# OxygenSensor.net
KiCad netlist of a schematic drawn in Altium Designer
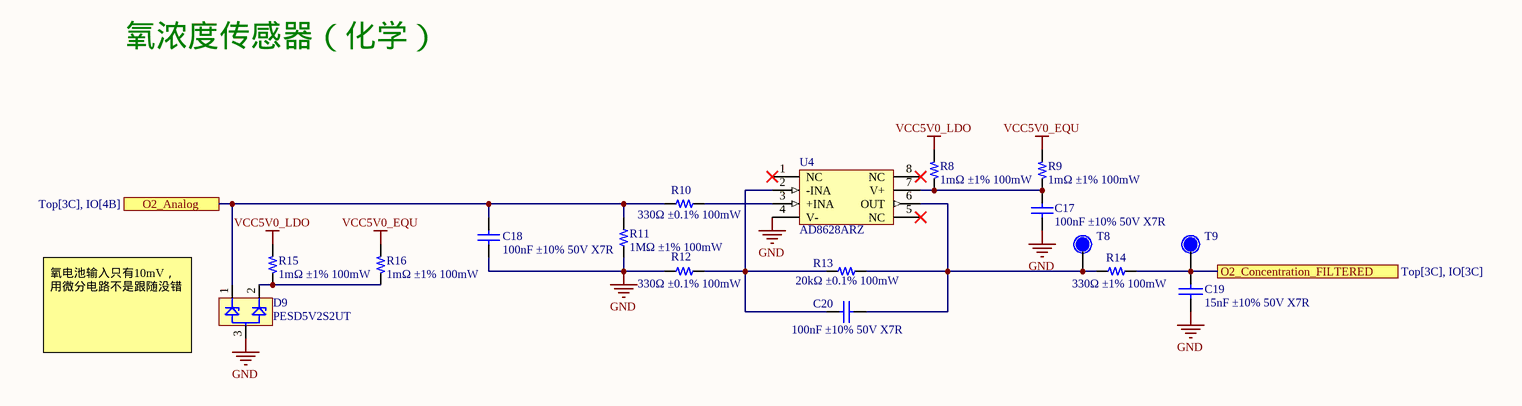
[diagram p0: OxygenSensor.SchDoc]

(export (version "E")
  (design (tool "Eeschema 10.0.6"))
  (components
    (comp (ref "C17")
      (value "100nF ±10% 50V X7R")
      (footprint "C-0603")
      (libsource (lib "电容") (part "100nF_1"))
    )
    (comp (ref "C18")
      (value "100nF ±10% 50V X7R")
      (footprint "C-0603")
      (libsource (lib "电容") (part "100nF_1"))
    )
    (comp (ref "C19")
      (value "15nF ±10% 50V X7R")
      (footprint "C-0603")
      (description "Capacitor")
      (libsource (lib "*") (part "CAP"))
    )
    (comp (ref "C20")
      (value "100nF ±10% 50V X7R")
      (footprint "C-0603")
      (libsource (lib "电容") (part "100nF_1"))
    )
    (comp (ref "D9") (value "PESD5V2S2UT") (footprint "sot23-3") (libsource (lib "IC") (part "PESDxS2UT")))
    (comp (ref "R8")
      (value "1mΩ ±1% 100mW")
      (footprint "R-0603")
      (description "国巨\r\n1mΩ ±1% 100mW")
      (libsource (lib "电阻") (part "10K_1"))
    )
    (comp (ref "R9")
      (value "1mΩ ±1% 100mW")
      (footprint "R-0603")
      (description "国巨\r\n1mΩ ±1% 100mW")
      (libsource (lib "电阻") (part "10K_1"))
    )
    (comp (ref "R10")
      (value "330Ω ±0.1% 100mW")
      (footprint "R-0603")
      (description "国巨RC0805FR-07330R")
      (libsource (lib "电阻") (part "330Ω_1"))
    )
    (comp (ref "R11") (value "1MΩ ±1% 100mW") (footprint "R-0603") (libsource (lib "Device") (part "R-0603")))
    (comp (ref "R12")
      (value "330Ω ±0.1% 100mW")
      (footprint "R-0603")
      (description "国巨RC0805FR-07330R")
      (libsource (lib "电阻") (part "330Ω_1"))
    )
    (comp (ref "R13")
      (value "20kΩ ±0.1% 100mW")
      (footprint "R-0603")
      (description "国巨RC0805FR-0712K")
      (libsource (lib "电阻") (part "12K_1"))
    )
    (comp (ref "R14")
      (value "330Ω ±1% 100mW")
      (footprint "R-0603")
      (libsource (lib "Device") (part "R-0603"))
    )
    (comp (ref "R15")
      (value "1mΩ ±1% 100mW")
      (footprint "R-0603")
      (description "国巨\r\n1mΩ ±1% 100mW")
      (libsource (lib "电阻") (part "10K_1"))
    )
    (comp (ref "R16")
      (value "1mΩ ±1% 100mW")
      (footprint "R-0603")
      (description "国巨\r\n1mΩ ±1% 100mW")
      (libsource (lib "电阻") (part "10K_1"))
    )
    (comp (ref "T8")
      (value "Test?")
      (footprint "TestPad_SMD")
      (description "TestPad_SMD")
      (libsource (lib "Component") (part "TestPad_SMD"))
    )
    (comp (ref "T9")
      (value "Test?")
      (footprint "TestPad_SMD")
      (description "TestPad_SMD")
      (libsource (lib "Component") (part "TestPad_SMD"))
    )
    (comp (ref "U4") (value "AD8628ARZ") (footprint "SOIC8") (libsource (lib "IC") (part "AD8628ARZ")))
  )
  (nets
    (net (code "1") (name "/O2_Analog") (class "Default")
      (node (ref "C18") (pin "2") (pinfunction "2_2") (pintype "passive"))
      (node (ref "D9") (pin "1") (pinfunction "1_1") (pintype "passive"))
      (node (ref "R10") (pin "1") (pinfunction "TOP_1") (pintype "passive"))
      (node (ref "R11") (pin "1") (pinfunction "1_1") (pintype "passive"))
    )
    (net (code "2") (name "/O2_Concentration_FILTERED") (class "Default")
      (node (ref "C19") (pin "2") (pinfunction "2_2") (pintype "passive"))
      (node (ref "R14") (pin "1") (pinfunction "1_1") (pintype "passive"))
      (node (ref "T9") (pin "1") (pinfunction "1_1") (pintype "passive"))
    )
    (net (code "3") (name "GND") (class "Default")
      (node (ref "C17") (pin "2") (pinfunction "2_2") (pintype "passive"))
      (node (ref "C18") (pin "1") (pinfunction "1_1") (pintype "passive"))
      (node (ref "C19") (pin "1") (pinfunction "1_1") (pintype "passive"))
      (node (ref "D9") (pin "3") (pinfunction "3_3") (pintype "passive"))
      (node (ref "R11") (pin "2") (pinfunction "2_2") (pintype "passive"))
      (node (ref "R12") (pin "1") (pinfunction "TOP_1") (pintype "passive"))
      (node (ref "U4") (pin "4") (pinfunction "V-_4") (pintype "passive"))
    )
    (net (code "4") (name "Net-(R8-TOP)") (class "Default")
      (node (ref "C17") (pin "1") (pinfunction "1_1") (pintype "passive"))
      (node (ref "R8") (pin "1") (pinfunction "TOP_1") (pintype "passive"))
      (node (ref "R9") (pin "1") (pinfunction "TOP_1") (pintype "passive"))
      (node (ref "U4") (pin "7") (pinfunction "V+_7") (pintype "power_in"))
    )
    (net (code "5") (name "Net-(R10-BOT)") (class "Default")
      (node (ref "R10") (pin "2") (pinfunction "BOT_2") (pintype "passive"))
      (node (ref "U4") (pin "3") (pinfunction "+INA_3") (pintype "input"))
    )
    (net (code "6") (name "Net-(R12-BOT)") (class "Default")
      (node (ref "C20") (pin "1") (pinfunction "1_1") (pintype "passive"))
      (node (ref "R12") (pin "2") (pinfunction "BOT_2") (pintype "passive"))
      (node (ref "R13") (pin "1") (pinfunction "TOP_1") (pintype "passive"))
      (node (ref "U4") (pin "2") (pinfunction "-INA_2") (pintype "input"))
    )
    (net (code "7") (name "Net-(R13-BOT)") (class "Default")
      (node (ref "C20") (pin "2") (pinfunction "2_2") (pintype "passive"))
      (node (ref "R13") (pin "2") (pinfunction "BOT_2") (pintype "passive"))
      (node (ref "R14") (pin "2") (pinfunction "2_2") (pintype "passive"))
      (node (ref "T8") (pin "1") (pinfunction "1_1") (pintype "passive"))
      (node (ref "U4") (pin "6") (pinfunction "OUT_6") (pintype "output"))
    )
    (net (code "8") (name "Net-(R15-TOP)") (class "Default")
      (node (ref "D9") (pin "2") (pinfunction "2_2") (pintype "passive"))
      (node (ref "R15") (pin "1") (pinfunction "TOP_1") (pintype "passive"))
      (node (ref "R16") (pin "1") (pinfunction "TOP_1") (pintype "passive"))
    )
    (net (code "9") (name "VCC5V0_EQU") (class "Default")
      (node (ref "R16") (pin "2") (pinfunction "BOT_2") (pintype "passive"))
      (node (ref "R9") (pin "2") (pinfunction "BOT_2") (pintype "passive"))
    )
    (net (code "10") (name "VCC5V0_LDO") (class "Default")
      (node (ref "R15") (pin "2") (pinfunction "BOT_2") (pintype "passive"))
      (node (ref "R8") (pin "2") (pinfunction "BOT_2") (pintype "passive"))
    )
    (net (code "11") (name "unconnected-(U4-NC-Pad1)") (class "Default")
      (node (ref "U4") (pin "1") (pinfunction "NC_1") (pintype "tri_state+no_connect"))
    )
    (net (code "12") (name "unconnected-(U4-NC-Pad5)") (class "Default")
      (node (ref "U4") (pin "5") (pinfunction "NC_5") (pintype "tri_state+no_connect"))
    )
    (net (code "13") (name "unconnected-(U4-NC-Pad8)") (class "Default")
      (node (ref "U4") (pin "8") (pinfunction "NC_8") (pintype "tri_state+no_connect"))
    )
  )
)
